# pcb_poinsettia.net
KiCad netlist of a schematic drawn in EAGLE
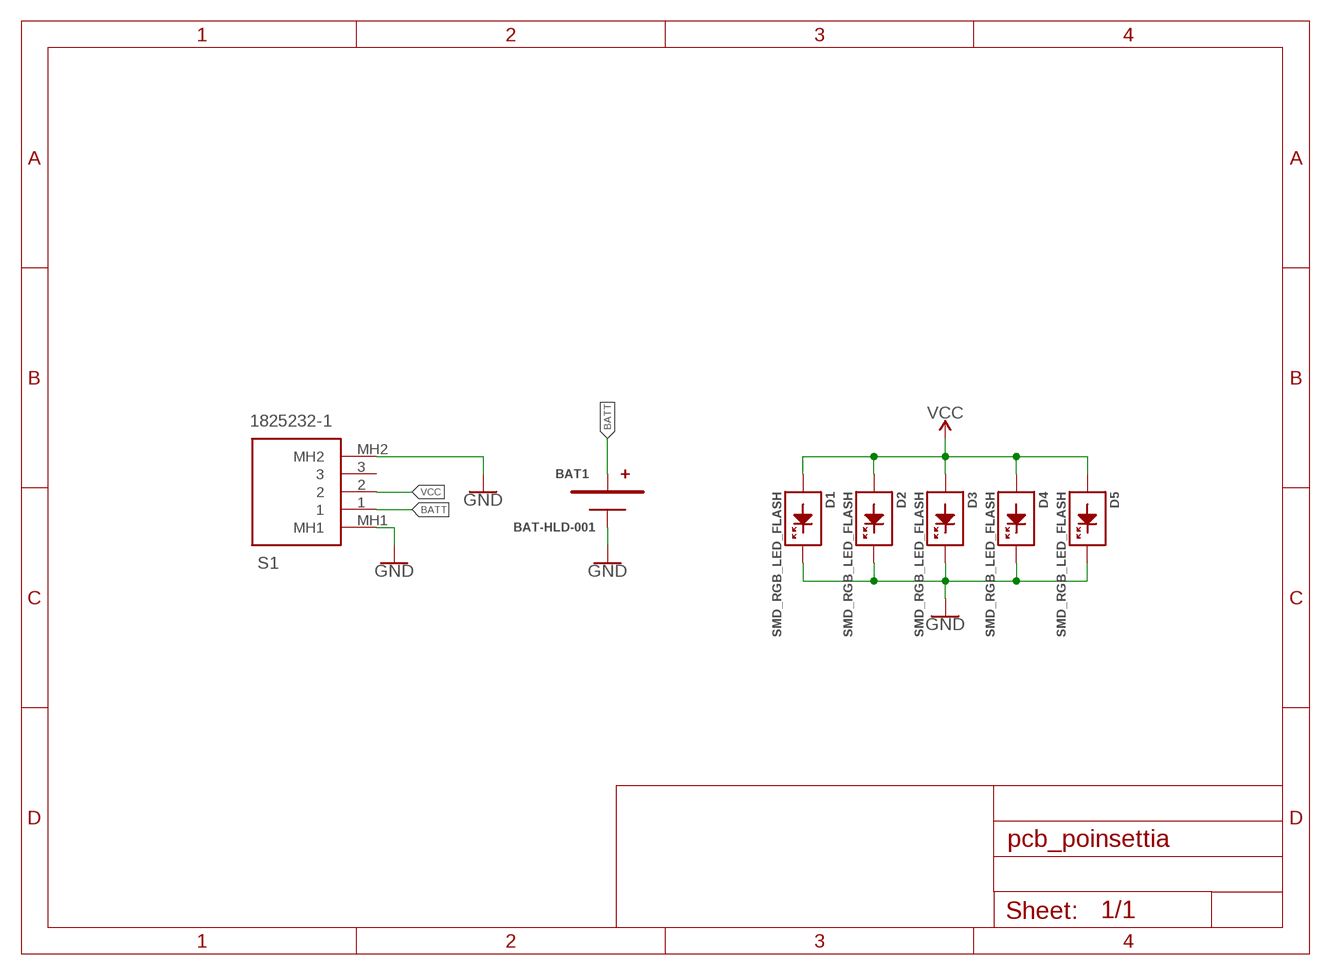
[diagram p0: schematic, sheet 1]

(export (version "E")
  (design (tool "Eeschema 10.0.6"))
  (components
    (comp (ref "BAT1")
      (value "BAT-HLD-001")
      (footprint "eagle-import:BATHLD001")
      (fields
        (field (name "MANUFACTURER#PART") "BAT-HLD-001-TR ")
        (field (name "MOUSER#PART") "712-BAT-HLD-001-TR ")
      )
      (libsource (lib "eagle-import") (part "BAT-HLD-001"))
    )
    (comp (ref "D1")
      (value "SMD_RGB_LED_FLASH")
      (footprint "eagle-import:SMD_RGB_LED_0807")
      (libsource (lib "eagle-import") (part "SMD_RGB_LED_FLASH"))
    )
    (comp (ref "D2")
      (value "SMD_RGB_LED_FLASH")
      (footprint "eagle-import:SMD_RGB_LED_0807")
      (libsource (lib "eagle-import") (part "SMD_RGB_LED_FLASH"))
    )
    (comp (ref "D3")
      (value "SMD_RGB_LED_FLASH")
      (footprint "eagle-import:SMD_RGB_LED_0807")
      (libsource (lib "eagle-import") (part "SMD_RGB_LED_FLASH"))
    )
    (comp (ref "D4")
      (value "SMD_RGB_LED_FLASH")
      (footprint "eagle-import:SMD_RGB_LED_0807")
      (libsource (lib "eagle-import") (part "SMD_RGB_LED_FLASH"))
    )
    (comp (ref "D5")
      (value "SMD_RGB_LED_FLASH")
      (footprint "eagle-import:SMD_RGB_LED_0807")
      (libsource (lib "eagle-import") (part "SMD_RGB_LED_FLASH"))
    )
    (comp (ref "S1")
      (value "1825232-1")
      (footprint "eagle-import:18252321")
      (fields (field (name "MOUSER_PART_NUMBER") "655-1825232-1"))
      (libsource (lib "eagle-import") (part "1825232-1"))
    )
  )
  (nets
    (net (code "1") (name "BATT") (class "Default")
      (node (ref "BAT1") (pin "1") (pinfunction "P_1") (pintype "bidirectional"))
      (node (ref "BAT1") (pin "2") (pinfunction "P_2") (pintype "bidirectional"))
      (node (ref "S1") (pin "1") (pinfunction "1_1") (pintype "bidirectional"))
    )
    (net (code "2") (name "GND") (class "Default")
      (node (ref "BAT1") (pin "3") (pinfunction "N_3") (pintype "bidirectional"))
      (node (ref "D1") (pin "3") (pinfunction "K_3") (pintype "bidirectional"))
      (node (ref "D1") (pin "4") (pinfunction "K_4") (pintype "bidirectional"))
      (node (ref "D2") (pin "3") (pinfunction "K_3") (pintype "bidirectional"))
      (node (ref "D2") (pin "4") (pinfunction "K_4") (pintype "bidirectional"))
      (node (ref "D3") (pin "3") (pinfunction "K_3") (pintype "bidirectional"))
      (node (ref "D3") (pin "4") (pinfunction "K_4") (pintype "bidirectional"))
      (node (ref "D4") (pin "3") (pinfunction "K_3") (pintype "bidirectional"))
      (node (ref "D4") (pin "4") (pinfunction "K_4") (pintype "bidirectional"))
      (node (ref "D5") (pin "3") (pinfunction "K_3") (pintype "bidirectional"))
      (node (ref "D5") (pin "4") (pinfunction "K_4") (pintype "bidirectional"))
      (node (ref "S1") (pin "MH1") (pinfunction "MH1_MH1") (pintype "bidirectional"))
      (node (ref "S1") (pin "MH2") (pinfunction "MH2_MH2") (pintype "bidirectional"))
    )
    (net (code "3") (name "VCC") (class "Default")
      (node (ref "D1") (pin "1") (pinfunction "A_1") (pintype "bidirectional"))
      (node (ref "D1") (pin "2") (pinfunction "A_2") (pintype "bidirectional"))
      (node (ref "D2") (pin "1") (pinfunction "A_1") (pintype "bidirectional"))
      (node (ref "D2") (pin "2") (pinfunction "A_2") (pintype "bidirectional"))
      (node (ref "D3") (pin "1") (pinfunction "A_1") (pintype "bidirectional"))
      (node (ref "D3") (pin "2") (pinfunction "A_2") (pintype "bidirectional"))
      (node (ref "D4") (pin "1") (pinfunction "A_1") (pintype "bidirectional"))
      (node (ref "D4") (pin "2") (pinfunction "A_2") (pintype "bidirectional"))
      (node (ref "D5") (pin "1") (pinfunction "A_1") (pintype "bidirectional"))
      (node (ref "D5") (pin "2") (pinfunction "A_2") (pintype "bidirectional"))
      (node (ref "S1") (pin "2") (pinfunction "2_2") (pintype "bidirectional"))
    )
    (net (code "4") (name "unconnected-(S1-Pad3)") (class "Default")
      (node (ref "S1") (pin "3") (pinfunction "3_3") (pintype "bidirectional"))
    )
  )
)
